# APDS-Breakout.net
KiCad netlist of a schematic drawn in EAGLE
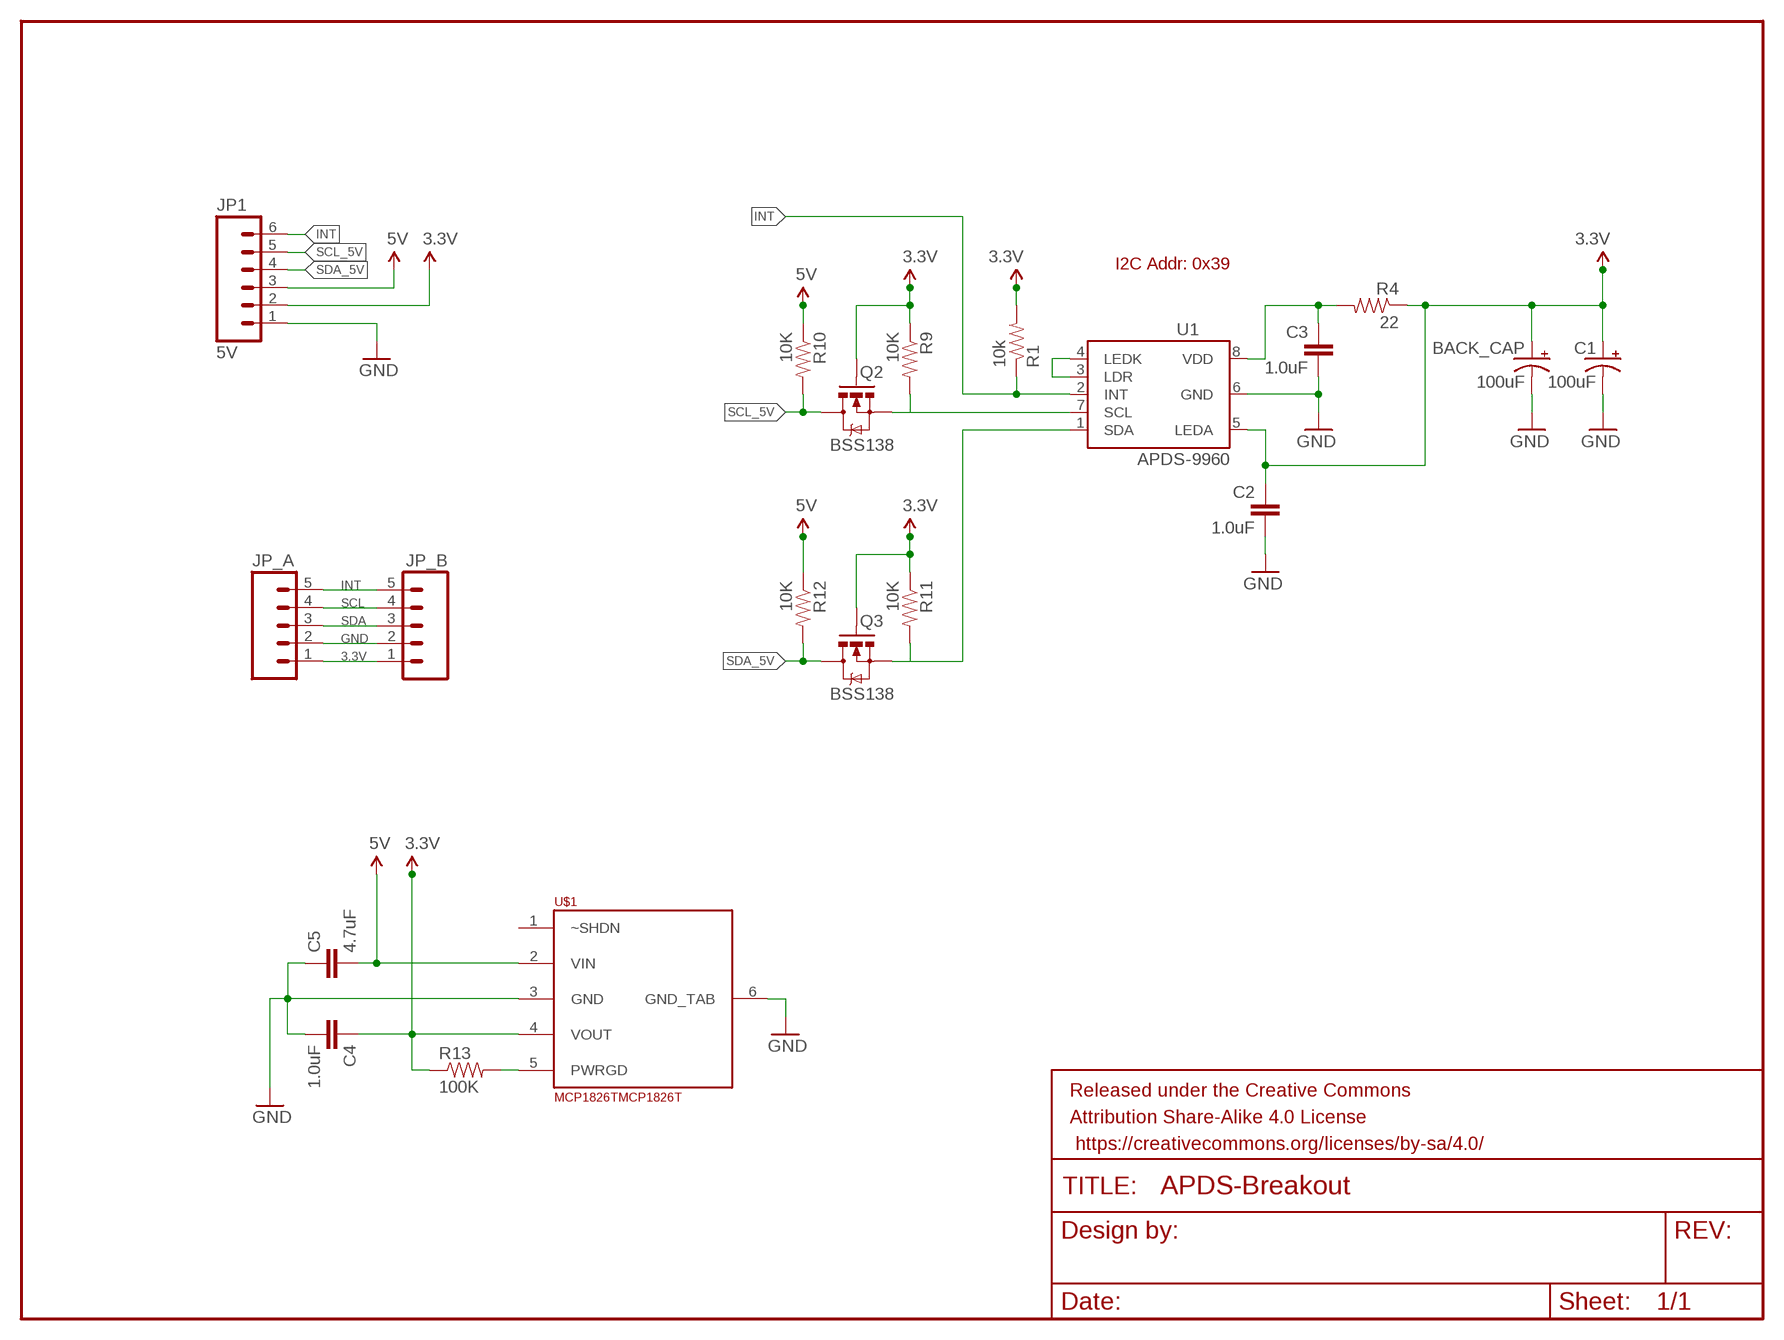
[diagram p0: schematic, sheet 1]

(export (version "E")
  (design (tool "Eeschema 10.0.6"))
  (components
    (comp (ref "BACK_CAP")
      (value "100uF")
      (footprint "eagle-import:EIA7343")
      (libsource (lib "eagle-import") (part "100UF-10V-10%(TANT)"))
    )
    (comp (ref "C1")
      (value "100uF")
      (footprint "eagle-import:EIA7343")
      (libsource (lib "eagle-import") (part "100UF-10V-10%(TANT)"))
    )
    (comp (ref "C2")
      (value "1.0uF")
      (footprint "eagle-import:0603-CAP")
      (libsource (lib "eagle-import") (part "1.0UF-16V-10%(0603)"))
    )
    (comp (ref "C3")
      (value "1.0uF")
      (footprint "eagle-import:0603-CAP")
      (libsource (lib "eagle-import") (part "1.0UF-16V-10%(0603)"))
    )
    (comp (ref "C4")
      (value "1.0uF")
      (footprint "eagle-import:0603-CAP")
      (libsource (lib "eagle-import") (part "1.0UF-16V-10%(0603)"))
    )
    (comp (ref "C5")
      (value "4.7uF")
      (footprint "eagle-import:0603-CAP")
      (libsource (lib "eagle-import") (part "1.0UF-16V-10%(0603)"))
    )
    (comp (ref "FRAME1")
      (value "FRAME-LETTER")
      (footprint "eagle-import:CREATIVE_COMMONS")
      (libsource (lib "eagle-import") (part "FRAME-LETTER"))
    )
    (comp (ref "JP1")
      (value "5V")
      (footprint "eagle-import:1X06_NO_SILK")
      (libsource (lib "eagle-import") (part "M06NO_SILK_FEMALE_PTH"))
    )
    (comp (ref "JP_A")
      (value "M05PTH")
      (footprint "eagle-import:1X05")
      (libsource (lib "eagle-import") (part "M05PTH"))
    )
    (comp (ref "JP_B")
      (value "M05PTH")
      (footprint "eagle-import:1X05")
      (libsource (lib "eagle-import") (part "M05PTH"))
    )
    (comp (ref "Q2")
      (value "BSS138")
      (footprint "eagle-import:SOT23-3")
      (libsource (lib "eagle-import") (part "MOSFET-NCHANNELSMD"))
    )
    (comp (ref "Q3")
      (value "BSS138")
      (footprint "eagle-import:SOT23-3")
      (libsource (lib "eagle-import") (part "MOSFET-NCHANNELSMD"))
    )
    (comp (ref "R1")
      (value "10k")
      (footprint "eagle-import:0603-RES")
      (libsource (lib "eagle-import") (part "10KOHM1/10W1%(0603)0603"))
    )
    (comp (ref "R4")
      (value "22")
      (footprint "eagle-import:0603-RES")
      (libsource (lib "eagle-import") (part "RESISTOR0603"))
    )
    (comp (ref "R9")
      (value "10K")
      (footprint "eagle-import:0603-RES")
      (libsource (lib "eagle-import") (part "RESISTOR0603-RES"))
    )
    (comp (ref "R10")
      (value "10K")
      (footprint "eagle-import:0603-RES")
      (libsource (lib "eagle-import") (part "RESISTOR0603-RES"))
    )
    (comp (ref "R11")
      (value "10K")
      (footprint "eagle-import:0603-RES")
      (libsource (lib "eagle-import") (part "RESISTOR0603-RES"))
    )
    (comp (ref "R12")
      (value "10K")
      (footprint "eagle-import:0603-RES")
      (libsource (lib "eagle-import") (part "RESISTOR0603-RES"))
    )
    (comp (ref "R13")
      (value "100K")
      (footprint "eagle-import:0603-RES")
      (libsource (lib "eagle-import") (part "RESISTOR0603-RES"))
    )
    (comp (ref "U$1")
      (value "MCP1826TMCP1826T")
      (footprint "eagle-import:SOP-223-5")
      (libsource (lib "eagle-import") (part "MCP1826TMCP1826T"))
    )
    (comp (ref "U1")
      (value "APDS-9960")
      (footprint "eagle-import:APDS-9960")
      (libsource (lib "eagle-import") (part "APDS-9960"))
    )
  )
  (nets
    (net (code "1") (name "/SCL") (class "Default")
      (node (ref "JP_A") (pin "4") (pinfunction "4_4") (pintype "passive"))
      (node (ref "JP_B") (pin "4") (pinfunction "4_4") (pintype "passive"))
      (node (ref "Q2") (pin "2") (pinfunction "S_2") (pintype "passive"))
      (node (ref "R9") (pin "2") (pinfunction "2_2") (pintype "passive"))
      (node (ref "U1") (pin "7") (pinfunction "SCL_7") (pintype "bidirectional"))
    )
    (net (code "2") (name "/SDA") (class "Default")
      (node (ref "JP_A") (pin "3") (pinfunction "3_3") (pintype "passive"))
      (node (ref "JP_B") (pin "3") (pinfunction "3_3") (pintype "passive"))
      (node (ref "Q3") (pin "2") (pinfunction "S_2") (pintype "passive"))
      (node (ref "R11") (pin "2") (pinfunction "2_2") (pintype "passive"))
      (node (ref "U1") (pin "1") (pinfunction "SDA_1") (pintype "bidirectional"))
    )
    (net (code "3") (name "3.3V") (class "Default")
      (node (ref "BACK_CAP") (pin "A") (pinfunction "+_A") (pintype "passive"))
      (node (ref "C1") (pin "A") (pinfunction "+_A") (pintype "passive"))
      (node (ref "C2") (pin "1") (pinfunction "1_1") (pintype "passive"))
      (node (ref "C4") (pin "1") (pinfunction "1_1") (pintype "passive"))
      (node (ref "JP1") (pin "2") (pinfunction "2_2") (pintype "passive"))
      (node (ref "JP_A") (pin "1") (pinfunction "1_1") (pintype "passive"))
      (node (ref "JP_B") (pin "1") (pinfunction "1_1") (pintype "passive"))
      (node (ref "Q2") (pin "1") (pinfunction "G_1") (pintype "passive"))
      (node (ref "Q3") (pin "1") (pinfunction "G_1") (pintype "passive"))
      (node (ref "R1") (pin "2") (pinfunction "2_2") (pintype "passive"))
      (node (ref "R11") (pin "1") (pinfunction "1_1") (pintype "passive"))
      (node (ref "R13") (pin "1") (pinfunction "1_1") (pintype "passive"))
      (node (ref "R4") (pin "1") (pinfunction "1_1") (pintype "passive"))
      (node (ref "R9") (pin "1") (pinfunction "1_1") (pintype "passive"))
      (node (ref "U$1") (pin "4") (pinfunction "VOUT_4") (pintype "bidirectional"))
      (node (ref "U1") (pin "5") (pinfunction "LEDA_5") (pintype "bidirectional"))
    )
    (net (code "4") (name "5V") (class "Default")
      (node (ref "C5") (pin "2") (pinfunction "2_2") (pintype "passive"))
      (node (ref "JP1") (pin "3") (pinfunction "3_3") (pintype "passive"))
      (node (ref "R10") (pin "1") (pinfunction "1_1") (pintype "passive"))
      (node (ref "R12") (pin "1") (pinfunction "1_1") (pintype "passive"))
      (node (ref "U$1") (pin "2") (pinfunction "VIN_2") (pintype "bidirectional"))
    )
    (net (code "5") (name "GND") (class "Default")
      (node (ref "BACK_CAP") (pin "C") (pinfunction "-_C") (pintype "passive"))
      (node (ref "C1") (pin "C") (pinfunction "-_C") (pintype "passive"))
      (node (ref "C2") (pin "2") (pinfunction "2_2") (pintype "passive"))
      (node (ref "C3") (pin "2") (pinfunction "2_2") (pintype "passive"))
      (node (ref "C4") (pin "2") (pinfunction "2_2") (pintype "passive"))
      (node (ref "C5") (pin "1") (pinfunction "1_1") (pintype "passive"))
      (node (ref "JP1") (pin "1") (pinfunction "1_1") (pintype "passive"))
      (node (ref "JP_A") (pin "2") (pinfunction "2_2") (pintype "passive"))
      (node (ref "JP_B") (pin "2") (pinfunction "2_2") (pintype "passive"))
      (node (ref "U$1") (pin "3") (pinfunction "GND_3") (pintype "bidirectional"))
      (node (ref "U$1") (pin "6") (pinfunction "GND_TAB_6") (pintype "bidirectional"))
      (node (ref "U1") (pin "6") (pinfunction "GND_6") (pintype "bidirectional"))
    )
    (net (code "6") (name "INT") (class "Default")
      (node (ref "JP1") (pin "6") (pinfunction "6_6") (pintype "passive"))
      (node (ref "JP_A") (pin "5") (pinfunction "5_5") (pintype "passive"))
      (node (ref "JP_B") (pin "5") (pinfunction "5_5") (pintype "passive"))
      (node (ref "R1") (pin "1") (pinfunction "1_1") (pintype "passive"))
      (node (ref "U1") (pin "2") (pinfunction "INT_2") (pintype "bidirectional"))
    )
    (net (code "7") (name "Net-(U$1-PWRGD)") (class "Default")
      (node (ref "R13") (pin "2") (pinfunction "2_2") (pintype "passive"))
      (node (ref "U$1") (pin "5") (pinfunction "PWRGD_5") (pintype "bidirectional"))
    )
    (net (code "8") (name "Net-(U1-LDR)") (class "Default")
      (node (ref "U1") (pin "3") (pinfunction "LDR_3") (pintype "bidirectional"))
      (node (ref "U1") (pin "4") (pinfunction "LEDK_4") (pintype "bidirectional"))
    )
    (net (code "9") (name "Net-(U1-VDD)") (class "Default")
      (node (ref "C3") (pin "1") (pinfunction "1_1") (pintype "passive"))
      (node (ref "R4") (pin "2") (pinfunction "2_2") (pintype "passive"))
      (node (ref "U1") (pin "8") (pinfunction "VDD_8") (pintype "bidirectional"))
    )
    (net (code "10") (name "SCL_5V") (class "Default")
      (node (ref "JP1") (pin "5") (pinfunction "5_5") (pintype "passive"))
      (node (ref "Q2") (pin "3") (pinfunction "D_3") (pintype "passive"))
      (node (ref "R10") (pin "2") (pinfunction "2_2") (pintype "passive"))
    )
    (net (code "11") (name "SDA_5V") (class "Default")
      (node (ref "JP1") (pin "4") (pinfunction "4_4") (pintype "passive"))
      (node (ref "Q3") (pin "3") (pinfunction "D_3") (pintype "passive"))
      (node (ref "R12") (pin "2") (pinfunction "2_2") (pintype "passive"))
    )
    (net (code "12") (name "unconnected-(U$1-~{SHDN}-Pad1)") (class "Default")
      (node (ref "U$1") (pin "1") (pinfunction "~{SHDN}_1") (pintype "bidirectional"))
    )
  )
)
